# untitled.net
KiCad netlist of a schematic drawn in EAGLE
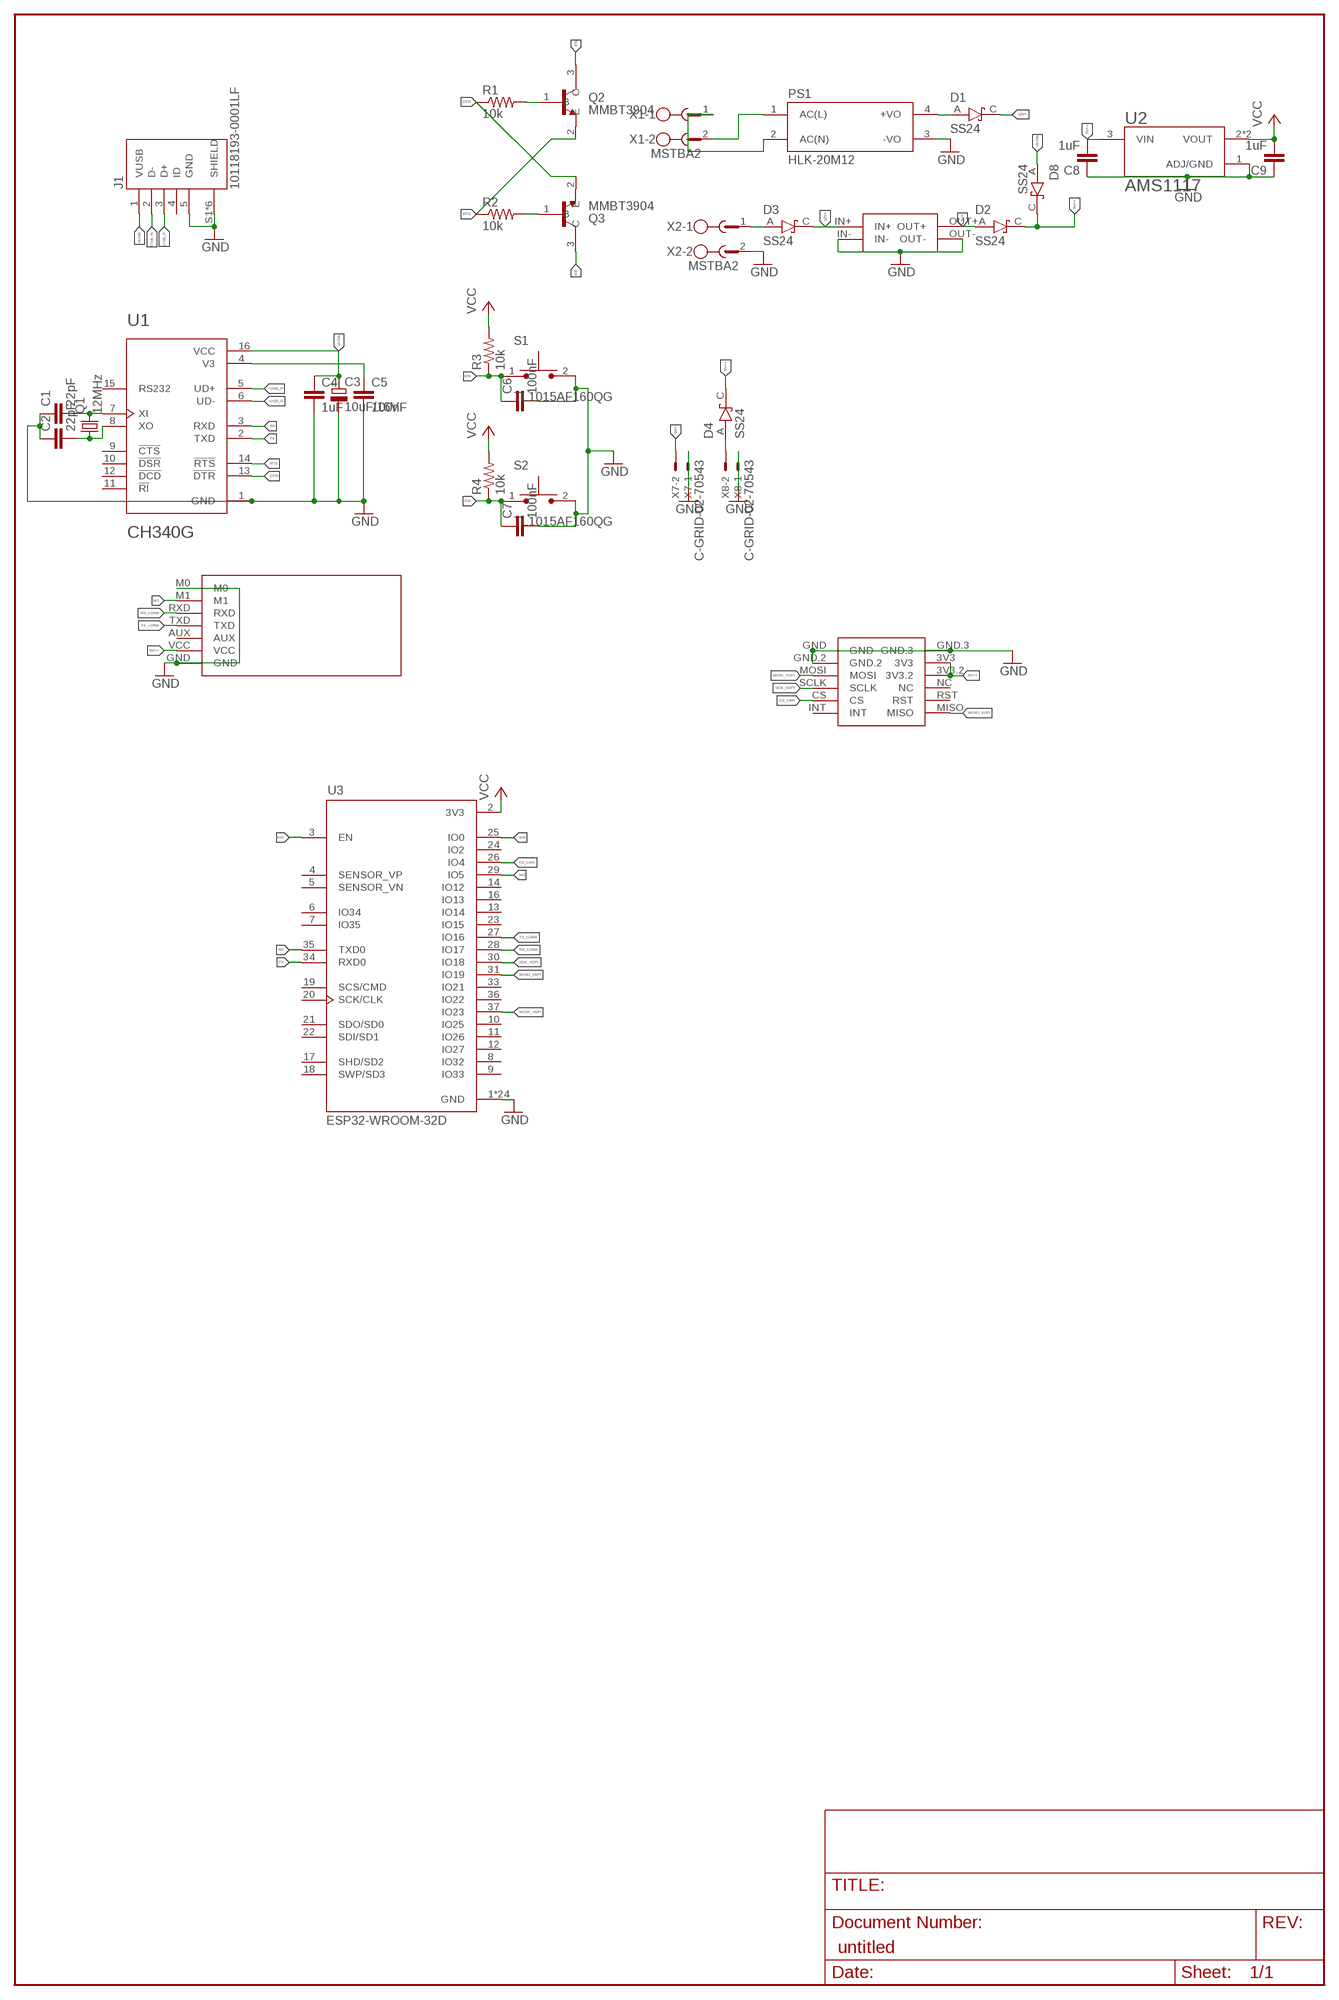
[diagram p0: schematic, sheet 1]

(export (version "E")
  (design (tool "Eeschema 10.0.6"))
  (components
    (comp (ref "C1")
      (value "22pF")
      (footprint "eagle-import:C0805K")
      (libsource (lib "eagle-import") (part "C-EUC0805K"))
    )
    (comp (ref "C2")
      (value "22pF")
      (footprint "eagle-import:C0805K")
      (libsource (lib "eagle-import") (part "C-EUC0805K"))
    )
    (comp (ref "C3")
      (value "10uF/16V")
      (footprint "eagle-import:153CLV-0505")
      (libsource (lib "eagle-import") (part "CPOL-EU153CLV-0505"))
    )
    (comp (ref "C4")
      (value "1uF")
      (footprint "eagle-import:C0805K")
      (libsource (lib "eagle-import") (part "C-EUC0805K"))
    )
    (comp (ref "C5")
      (value "100nF")
      (footprint "eagle-import:C0805K")
      (libsource (lib "eagle-import") (part "C-EUC0805K"))
    )
    (comp (ref "C6")
      (value "100nF")
      (footprint "eagle-import:C0805K")
      (libsource (lib "eagle-import") (part "C-EUC0805K"))
    )
    (comp (ref "C7")
      (value "100nF")
      (footprint "eagle-import:C0805K")
      (libsource (lib "eagle-import") (part "C-EUC0805K"))
    )
    (comp (ref "C8")
      (value "1uF")
      (footprint "eagle-import:C0805K")
      (libsource (lib "eagle-import") (part "C-EUC0805K"))
    )
    (comp (ref "C9")
      (value "1uF")
      (footprint "eagle-import:C0805K")
      (libsource (lib "eagle-import") (part "C-EUC0805K"))
    )
    (comp (ref "D1")
      (value "SS24")
      (footprint "eagle-import:DIOM5336X265N")
      (fields (field (name "MF") "ON Semiconductor"))
      (libsource (lib "eagle-import") (part "SS24"))
    )
    (comp (ref "D2")
      (value "SS24")
      (footprint "eagle-import:DIOM5336X265N")
      (fields (field (name "MF") "ON Semiconductor"))
      (libsource (lib "eagle-import") (part "SS24"))
    )
    (comp (ref "D3")
      (value "SS24")
      (footprint "eagle-import:DIOM5336X265N")
      (fields (field (name "MF") "ON Semiconductor"))
      (libsource (lib "eagle-import") (part "SS24"))
    )
    (comp (ref "D4")
      (value "SS24")
      (footprint "eagle-import:DIOM5336X265N")
      (fields (field (name "MF") "ON Semiconductor"))
      (libsource (lib "eagle-import") (part "SS24"))
    )
    (comp (ref "D8")
      (value "SS24")
      (footprint "eagle-import:DIOM5336X265N")
      (fields (field (name "MF") "ON Semiconductor"))
      (libsource (lib "eagle-import") (part "SS24"))
    )
    (comp (ref "EBYTEE220-900T22D1")
      (value "EBYTEE220-900T22D")
      (footprint "eagle-import:EBYTEE220-900T22D")
      (libsource (lib "eagle-import") (part "EBYTEE220-900T22D"))
    )
    (comp (ref "J1")
      (value "10118193-0001LF")
      (footprint "eagle-import:FCI_10118193-0001LF")
      (fields (field (name "MF") "FCI"))
      (libsource (lib "eagle-import") (part "10118193-0001LF"))
    )
    (comp (ref "MINI1")
      (value "MINI560")
      (footprint "eagle-import:MINI560")
      (libsource (lib "eagle-import") (part "MINI560"))
    )
    (comp (ref "PS1")
      (value "HLK-20M12")
      (footprint "eagle-import:CONV_HLK-20M12")
      (fields (field (name "MF") "Hi-link"))
      (libsource (lib "eagle-import") (part "HLK-20M12"))
    )
    (comp (ref "Q1")
      (value "12MHz")
      (footprint "eagle-import:SM49")
      (libsource (lib "eagle-import") (part "CRYSTALSM49"))
    )
    (comp (ref "Q2")
      (value "MMBT3904")
      (footprint "eagle-import:SOT95P240X120-3N")
      (fields (field (name "MF") "ON Semiconductor"))
      (libsource (lib "eagle-import") (part "MMBT3904"))
    )
    (comp (ref "Q3")
      (value "MMBT3904")
      (footprint "eagle-import:SOT95P240X120-3N")
      (fields (field (name "MF") "ON Semiconductor"))
      (libsource (lib "eagle-import") (part "MMBT3904"))
    )
    (comp (ref "R1")
      (value "10k")
      (footprint "eagle-import:M0805")
      (libsource (lib "eagle-import") (part "R-US_M0805"))
    )
    (comp (ref "R2")
      (value "10k")
      (footprint "eagle-import:M0805")
      (libsource (lib "eagle-import") (part "R-US_M0805"))
    )
    (comp (ref "R3")
      (value "10k")
      (footprint "eagle-import:M0805")
      (libsource (lib "eagle-import") (part "R-US_M0805"))
    )
    (comp (ref "R4")
      (value "10k")
      (footprint "eagle-import:M0805")
      (libsource (lib "eagle-import") (part "R-US_M0805"))
    )
    (comp (ref "S1")
      (value "TL1015AF160QG")
      (footprint "eagle-import:SW_TL1015AF160QG")
      (fields (field (name "MF") "E-Switch"))
      (libsource (lib "eagle-import") (part "TL1015AF160QG"))
    )
    (comp (ref "S2")
      (value "TL1015AF160QG")
      (footprint "eagle-import:SW_TL1015AF160QG")
      (fields (field (name "MF") "E-Switch"))
      (libsource (lib "eagle-import") (part "TL1015AF160QG"))
    )
    (comp (ref "U$1")
      (value "MINI_W5500")
      (footprint "eagle-import:MINI_W5500")
      (libsource (lib "eagle-import") (part "MINI_W5500"))
    )
    (comp (ref "U1")
      (value "CH340G")
      (footprint "eagle-import:SOIC127P600X180-16N")
      (fields (field (name "MF") "WCH") (field (name "MP") "Ch340G"))
      (libsource (lib "eagle-import") (part "CH340G"))
    )
    (comp (ref "U2")
      (value "AMS1117")
      (footprint "eagle-import:SOT229P700X180-4N")
      (fields (field (name "MF") "Advanced Monolithic Systems"))
      (libsource (lib "eagle-import") (part "AMS1117"))
    )
    (comp (ref "U3")
      (value "ESP32-WROOM-32D")
      (footprint "eagle-import:MODULE_ESP32-WROOM-32D")
      (fields (field (name "MF") "Espressif Systems"))
      (libsource (lib "eagle-import") (part "ESP32-WROOM-32D"))
    )
    (comp (ref "X1")
      (value "MSTBA2")
      (footprint "eagle-import:MSTBA2")
      (fields (field (name "MF") "FARNELL") (field (name "MPN") "1757242"))
      (libsource (lib "eagle-import") (part "MSTBA2"))
    )
    (comp (ref "X2")
      (value "MSTBA2")
      (footprint "eagle-import:MSTBA2")
      (fields (field (name "MF") "FARNELL") (field (name "MPN") "1757242"))
      (libsource (lib "eagle-import") (part "MSTBA2"))
    )
    (comp (ref "X7")
      (value "C-GRID-02-70543")
      (footprint "eagle-import:70543-02")
      (fields (field (name "MF") "MOLEX"))
      (libsource (lib "eagle-import") (part "C-GRID-02-70543"))
    )
    (comp (ref "X8")
      (value "C-GRID-02-70543")
      (footprint "eagle-import:70543-02")
      (fields (field (name "MF") "MOLEX"))
      (libsource (lib "eagle-import") (part "C-GRID-02-70543"))
    )
  )
  (nets
    (net (code "1") (name "5V+") (class "Default")
      (node (ref "D2") (pin "A") (pinfunction "A_A") (pintype "passive"))
      (node (ref "MINI1") (pin "OUT+") (pinfunction "OUT+_OUT+") (pintype "bidirectional"))
      (node (ref "X7") (pin "2") (pinfunction "S_2") (pintype "passive"))
    )
    (net (code "2") (name "5V++") (class "Default")
      (node (ref "C8") (pin "2") (pinfunction "2_2") (pintype "passive"))
      (node (ref "D2") (pin "C") (pinfunction "K_C") (pintype "passive"))
      (node (ref "D4") (pin "C") (pinfunction "K_C") (pintype "passive"))
      (node (ref "D8") (pin "C") (pinfunction "K_C") (pintype "passive"))
      (node (ref "EBYTEE220-900T22D1") (pin "VCC") (pinfunction "VCC_VCC") (pintype "bidirectional"))
      (node (ref "U$1") (pin "3V3") (pinfunction "3V3_3V3") (pintype "bidirectional"))
      (node (ref "U$1") (pin "3V3.2") (pinfunction "3V3.2_3V3.2") (pintype "bidirectional"))
      (node (ref "U2") (pin "3") (pinfunction "VIN_3") (pintype "input"))
    )
    (net (code "3") (name "12V+") (class "Default")
      (node (ref "D1") (pin "C") (pinfunction "K_C") (pintype "passive"))
      (node (ref "D3") (pin "C") (pinfunction "K_C") (pintype "passive"))
      (node (ref "MINI1") (pin "IN+") (pinfunction "IN+_IN+") (pintype "bidirectional"))
    )
    (net (code "4") (name "CS_LAN") (class "Default")
      (node (ref "U$1") (pin "CS") (pinfunction "CS_CS") (pintype "bidirectional"))
      (node (ref "U3") (pin "26") (pinfunction "IO4_26") (pintype "bidirectional"))
    )
    (net (code "5") (name "DTR") (class "Default")
      (node (ref "Q3") (pin "2") (pinfunction "E_2") (pintype "passive"))
      (node (ref "R1") (pin "1") (pinfunction "1_1") (pintype "passive"))
      (node (ref "U1") (pin "13") (pinfunction "~{DTR}_13") (pintype "output"))
    )
    (net (code "6") (name "EN") (class "Default")
      (node (ref "C6") (pin "1") (pinfunction "1_1") (pintype "passive"))
      (node (ref "Q2") (pin "3") (pinfunction "C_3") (pintype "passive"))
      (node (ref "R3") (pin "1") (pinfunction "1_1") (pintype "passive"))
      (node (ref "S1") (pin "1") (pinfunction "1_1") (pintype "passive"))
      (node (ref "U3") (pin "3") (pinfunction "EN_3") (pintype "input"))
    )
    (net (code "7") (name "GND") (class "Default")
      (node (ref "C1") (pin "1") (pinfunction "1_1") (pintype "passive"))
      (node (ref "C2") (pin "1") (pinfunction "1_1") (pintype "passive"))
      (node (ref "C3") (pin "-") (pinfunction "-_-") (pintype "passive"))
      (node (ref "C4") (pin "2") (pinfunction "2_2") (pintype "passive"))
      (node (ref "C5") (pin "2") (pinfunction "2_2") (pintype "passive"))
      (node (ref "C6") (pin "2") (pinfunction "2_2") (pintype "passive"))
      (node (ref "C7") (pin "2") (pinfunction "2_2") (pintype "passive"))
      (node (ref "C8") (pin "1") (pinfunction "1_1") (pintype "passive"))
      (node (ref "C9") (pin "1") (pinfunction "1_1") (pintype "passive"))
      (node (ref "EBYTEE220-900T22D1") (pin "GND") (pinfunction "GND_GND") (pintype "bidirectional"))
      (node (ref "EBYTEE220-900T22D1") (pin "M0") (pinfunction "M0_M0") (pintype "bidirectional"))
      (node (ref "J1") (pin "5") (pinfunction "GND_5") (pintype "passive"))
      (node (ref "J1") (pin "S1") (pinfunction "SHIELD_S1") (pintype "passive"))
      (node (ref "J1") (pin "S2") (pinfunction "SHIELD_S2") (pintype "passive"))
      (node (ref "J1") (pin "S3") (pinfunction "SHIELD_S3") (pintype "passive"))
      (node (ref "J1") (pin "S4") (pinfunction "SHIELD_S4") (pintype "passive"))
      (node (ref "J1") (pin "S5") (pinfunction "SHIELD_S5") (pintype "passive"))
      (node (ref "J1") (pin "S6") (pinfunction "SHIELD_S6") (pintype "passive"))
      (node (ref "MINI1") (pin "IN-") (pinfunction "IN-_IN-") (pintype "bidirectional"))
      (node (ref "MINI1") (pin "OUT-") (pinfunction "OUT-_OUT-") (pintype "bidirectional"))
      (node (ref "PS1") (pin "3") (pinfunction "-VO_3") (pintype "output"))
      (node (ref "S1") (pin "2") (pinfunction "2_2") (pintype "passive"))
      (node (ref "S2") (pin "2") (pinfunction "2_2") (pintype "passive"))
      (node (ref "U$1") (pin "GND") (pinfunction "GND_GND") (pintype "bidirectional"))
      (node (ref "U$1") (pin "GND.2") (pinfunction "GND.2_GND.2") (pintype "bidirectional"))
      (node (ref "U$1") (pin "GND.3") (pinfunction "GND.3_GND.3") (pintype "bidirectional"))
      (node (ref "U1") (pin "1") (pinfunction "GND_1") (pintype "power_in"))
      (node (ref "U2") (pin "1") (pinfunction "ADJ/GND_1") (pintype "power_in"))
      (node (ref "U3") (pin "1") (pinfunction "GND_1") (pintype "power_in"))
      (node (ref "U3") (pin "15") (pinfunction "GND_15") (pintype "power_in"))
      (node (ref "U3") (pin "38") (pinfunction "GND_38") (pintype "power_in"))
      (node (ref "U3") (pin "39_1") (pinfunction "GND_39_1") (pintype "power_in"))
      (node (ref "U3") (pin "39_10") (pinfunction "GND_39_10") (pintype "power_in"))
      (node (ref "U3") (pin "39_11") (pinfunction "GND_39_11") (pintype "power_in"))
      (node (ref "U3") (pin "39_12") (pinfunction "GND_39_12") (pintype "power_in"))
      (node (ref "U3") (pin "39_13") (pinfunction "GND_39_13") (pintype "power_in"))
      (node (ref "U3") (pin "39_14") (pinfunction "GND_39_14") (pintype "power_in"))
      (node (ref "U3") (pin "39_15") (pinfunction "GND_39_15") (pintype "power_in"))
      (node (ref "U3") (pin "39_16") (pinfunction "GND_39_16") (pintype "power_in"))
      (node (ref "U3") (pin "39_17") (pinfunction "GND_39_17") (pintype "power_in"))
      (node (ref "U3") (pin "39_18") (pinfunction "GND_39_18") (pintype "power_in"))
      (node (ref "U3") (pin "39_19") (pinfunction "GND_39_19") (pintype "power_in"))
      (node (ref "U3") (pin "39_2") (pinfunction "GND_39_2") (pintype "power_in"))
      (node (ref "U3") (pin "39_20") (pinfunction "GND_39_20") (pintype "power_in"))
      (node (ref "U3") (pin "39_21") (pinfunction "GND_39_21") (pintype "power_in"))
      (node (ref "U3") (pin "39_3") (pinfunction "GND_39_3") (pintype "power_in"))
      (node (ref "U3") (pin "39_4") (pinfunction "GND_39_4") (pintype "power_in"))
      (node (ref "U3") (pin "39_5") (pinfunction "GND_39_5") (pintype "power_in"))
      (node (ref "U3") (pin "39_6") (pinfunction "GND_39_6") (pintype "power_in"))
      (node (ref "U3") (pin "39_7") (pinfunction "GND_39_7") (pintype "power_in"))
      (node (ref "U3") (pin "39_8") (pinfunction "GND_39_8") (pintype "power_in"))
      (node (ref "U3") (pin "39_9") (pinfunction "GND_39_9") (pintype "power_in"))
      (node (ref "X2") (pin "2") (pinfunction "1_2") (pintype "passive"))
      (node (ref "X7") (pin "1") (pinfunction "S_1") (pintype "passive"))
      (node (ref "X8") (pin "1") (pinfunction "S_1") (pintype "passive"))
    )
    (net (code "8") (name "IO0") (class "Default")
      (node (ref "C7") (pin "1") (pinfunction "1_1") (pintype "passive"))
      (node (ref "Q3") (pin "3") (pinfunction "C_3") (pintype "passive"))
      (node (ref "R4") (pin "1") (pinfunction "1_1") (pintype "passive"))
      (node (ref "S2") (pin "1") (pinfunction "1_1") (pintype "passive"))
      (node (ref "U3") (pin "25") (pinfunction "IO0_25") (pintype "bidirectional"))
    )
    (net (code "9") (name "M1") (class "Default")
      (node (ref "EBYTEE220-900T22D1") (pin "M1") (pinfunction "M1_M1") (pintype "bidirectional"))
      (node (ref "U3") (pin "29") (pinfunction "IO5_29") (pintype "bidirectional"))
    )
    (net (code "10") (name "MISO_VSPI") (class "Default")
      (node (ref "U$1") (pin "MISO") (pinfunction "MISO_MISO") (pintype "bidirectional"))
      (node (ref "U3") (pin "31") (pinfunction "IO19_31") (pintype "bidirectional"))
    )
    (net (code "11") (name "MOSI_VSPI") (class "Default")
      (node (ref "U$1") (pin "MOSI") (pinfunction "MOSI_MOSI") (pintype "bidirectional"))
      (node (ref "U3") (pin "37") (pinfunction "IO23_37") (pintype "bidirectional"))
    )
    (net (code "12") (name "Net-(D3-PadA)") (class "Default")
      (node (ref "D3") (pin "A") (pinfunction "A_A") (pintype "passive"))
      (node (ref "X2") (pin "1") (pinfunction "1_1") (pintype "passive"))
    )
    (net (code "13") (name "Net-(PS1-+VO)") (class "Default")
      (node (ref "D1") (pin "A") (pinfunction "A_A") (pintype "passive"))
      (node (ref "PS1") (pin "4") (pinfunction "+VO_4") (pintype "output"))
    )
    (net (code "14") (name "Net-(PS1-AC(L))") (class "Default")
      (node (ref "PS1") (pin "1") (pinfunction "AC(L)_1") (pintype "input"))
      (node (ref "X1") (pin "2") (pinfunction "1_2") (pintype "passive"))
    )
    (net (code "15") (name "Net-(PS1-AC(N))") (class "Default")
      (node (ref "PS1") (pin "2") (pinfunction "AC(N)_2") (pintype "input"))
      (node (ref "X1") (pin "1") (pinfunction "1_1") (pintype "passive"))
    )
    (net (code "16") (name "Net-(Q2-B)") (class "Default")
      (node (ref "Q2") (pin "1") (pinfunction "B_1") (pintype "passive"))
      (node (ref "R1") (pin "2") (pinfunction "2_2") (pintype "passive"))
    )
    (net (code "17") (name "Net-(Q3-B)") (class "Default")
      (node (ref "Q3") (pin "1") (pinfunction "B_1") (pintype "passive"))
      (node (ref "R2") (pin "2") (pinfunction "2_2") (pintype "passive"))
    )
    (net (code "18") (name "Net-(U1-V3)") (class "Default")
      (node (ref "C5") (pin "1") (pinfunction "1_1") (pintype "passive"))
      (node (ref "U1") (pin "4") (pinfunction "V3_4") (pintype "power_in"))
    )
    (net (code "19") (name "Net-(U1-XI)") (class "Default")
      (node (ref "C1") (pin "2") (pinfunction "2_2") (pintype "passive"))
      (node (ref "Q1") (pin "2") (pinfunction "2_2") (pintype "passive"))
      (node (ref "U1") (pin "7") (pinfunction "XI_7") (pintype "input"))
    )
    (net (code "20") (name "Net-(U1-XO)") (class "Default")
      (node (ref "C2") (pin "2") (pinfunction "2_2") (pintype "passive"))
      (node (ref "Q1") (pin "1") (pinfunction "1_1") (pintype "passive"))
      (node (ref "U1") (pin "8") (pinfunction "XO_8") (pintype "output"))
    )
    (net (code "21") (name "Net-(X8B-S)") (class "Default")
      (node (ref "D4") (pin "A") (pinfunction "A_A") (pintype "passive"))
      (node (ref "X8") (pin "2") (pinfunction "S_2") (pintype "passive"))
    )
    (net (code "22") (name "RTS") (class "Default")
      (node (ref "Q2") (pin "2") (pinfunction "E_2") (pintype "passive"))
      (node (ref "R2") (pin "1") (pinfunction "1_1") (pintype "passive"))
      (node (ref "U1") (pin "14") (pinfunction "~{RTS}_14") (pintype "output"))
    )
    (net (code "23") (name "RX") (class "Default")
      (node (ref "U1") (pin "3") (pinfunction "RXD_3") (pintype "input"))
      (node (ref "U3") (pin "35") (pinfunction "TXD0_35") (pintype "bidirectional"))
    )
    (net (code "24") (name "RX_LORA") (class "Default")
      (node (ref "EBYTEE220-900T22D1") (pin "RXD") (pinfunction "RXD_RXD") (pintype "bidirectional"))
      (node (ref "U3") (pin "28") (pinfunction "IO17_28") (pintype "bidirectional"))
    )
    (net (code "25") (name "SCK_VSPI") (class "Default")
      (node (ref "U$1") (pin "SCLK") (pinfunction "SCLK_SCLK") (pintype "bidirectional"))
      (node (ref "U3") (pin "30") (pinfunction "IO18_30") (pintype "bidirectional"))
    )
    (net (code "26") (name "TX") (class "Default")
      (node (ref "U1") (pin "2") (pinfunction "TXD_2") (pintype "output"))
      (node (ref "U3") (pin "34") (pinfunction "RXD0_34") (pintype "bidirectional"))
    )
    (net (code "27") (name "TX_LORA") (class "Default")
      (node (ref "EBYTEE220-900T22D1") (pin "TXD") (pinfunction "TXD_TXD") (pintype "bidirectional"))
      (node (ref "U3") (pin "27") (pinfunction "IO16_27") (pintype "bidirectional"))
    )
    (net (code "28") (name "USB_N") (class "Default")
      (node (ref "J1") (pin "2") (pinfunction "D-_2") (pintype "passive"))
      (node (ref "U1") (pin "6") (pinfunction "UD-_6") (pintype "bidirectional"))
    )
    (net (code "29") (name "USB_P") (class "Default")
      (node (ref "J1") (pin "3") (pinfunction "D+_3") (pintype "passive"))
      (node (ref "U1") (pin "5") (pinfunction "UD+_5") (pintype "bidirectional"))
    )
    (net (code "30") (name "VCC") (class "Default")
      (node (ref "C9") (pin "2") (pinfunction "2_2") (pintype "passive"))
      (node (ref "R3") (pin "2") (pinfunction "2_2") (pintype "passive"))
      (node (ref "R4") (pin "2") (pinfunction "2_2") (pintype "passive"))
      (node (ref "U2") (pin "2") (pinfunction "VOUT_2") (pintype "output"))
      (node (ref "U2") (pin "4") (pinfunction "VOUT_4") (pintype "output"))
      (node (ref "U3") (pin "2") (pinfunction "3V3_2") (pintype "power_in"))
    )
    (net (code "31") (name "VUSB") (class "Default")
      (node (ref "C3") (pin "+") (pinfunction "+_+") (pintype "passive"))
      (node (ref "C4") (pin "1") (pinfunction "1_1") (pintype "passive"))
      (node (ref "D8") (pin "A") (pinfunction "A_A") (pintype "passive"))
      (node (ref "J1") (pin "1") (pinfunction "VUSB_1") (pintype "passive"))
      (node (ref "U1") (pin "16") (pinfunction "VCC_16") (pintype "power_in"))
    )
    (net (code "32") (name "unconnected-(EBYTEE220-900T22D1-PadAUX)") (class "Default")
      (node (ref "EBYTEE220-900T22D1") (pin "AUX") (pinfunction "AUX_AUX") (pintype "bidirectional"))
    )
    (net (code "33") (name "unconnected-(J1-ID-Pad4)") (class "Default")
      (node (ref "J1") (pin "4") (pinfunction "ID_4") (pintype "passive"))
    )
    (net (code "34") (name "unconnected-(U$1-PadINT)") (class "Default")
      (node (ref "U$1") (pin "INT") (pinfunction "INT_INT") (pintype "bidirectional"))
    )
    (net (code "35") (name "unconnected-(U$1-PadNC)") (class "Default")
      (node (ref "U$1") (pin "NC") (pinfunction "NC_NC") (pintype "bidirectional"))
    )
    (net (code "36") (name "unconnected-(U$1-PadRST)") (class "Default")
      (node (ref "U$1") (pin "RST") (pinfunction "RST_RST") (pintype "bidirectional"))
    )
    (net (code "37") (name "unconnected-(U1-RS232-Pad15)") (class "Default")
      (node (ref "U1") (pin "15") (pinfunction "RS232_15") (pintype "input"))
    )
    (net (code "38") (name "unconnected-(U1-~{CTS}-Pad9)") (class "Default")
      (node (ref "U1") (pin "9") (pinfunction "~{CTS}_9") (pintype "input"))
    )
    (net (code "39") (name "unconnected-(U1-~{DCD}-Pad12)") (class "Default")
      (node (ref "U1") (pin "12") (pinfunction "~{DCD}_12") (pintype "input"))
    )
    (net (code "40") (name "unconnected-(U1-~{DSR}-Pad10)") (class "Default")
      (node (ref "U1") (pin "10") (pinfunction "~{DSR}_10") (pintype "input"))
    )
    (net (code "41") (name "unconnected-(U1-~{RI}-Pad11)") (class "Default")
      (node (ref "U1") (pin "11") (pinfunction "~{RI}_11") (pintype "input"))
    )
    (net (code "42") (name "unconnected-(U3-IO2-Pad24)") (class "Default")
      (node (ref "U3") (pin "24") (pinfunction "IO2_24") (pintype "bidirectional"))
    )
    (net (code "43") (name "unconnected-(U3-IO12-Pad14)") (class "Default")
      (node (ref "U3") (pin "14") (pinfunction "IO12_14") (pintype "bidirectional"))
    )
    (net (code "44") (name "unconnected-(U3-IO13-Pad16)") (class "Default")
      (node (ref "U3") (pin "16") (pinfunction "IO13_16") (pintype "bidirectional"))
    )
    (net (code "45") (name "unconnected-(U3-IO14-Pad13)") (class "Default")
      (node (ref "U3") (pin "13") (pinfunction "IO14_13") (pintype "bidirectional"))
    )
    (net (code "46") (name "unconnected-(U3-IO15-Pad23)") (class "Default")
      (node (ref "U3") (pin "23") (pinfunction "IO15_23") (pintype "bidirectional"))
    )
    (net (code "47") (name "unconnected-(U3-IO21-Pad33)") (class "Default")
      (node (ref "U3") (pin "33") (pinfunction "IO21_33") (pintype "bidirectional"))
    )
    (net (code "48") (name "unconnected-(U3-IO22-Pad36)") (class "Default")
      (node (ref "U3") (pin "36") (pinfunction "IO22_36") (pintype "bidirectional"))
    )
    (net (code "49") (name "unconnected-(U3-IO25-Pad10)") (class "Default")
      (node (ref "U3") (pin "10") (pinfunction "IO25_10") (pintype "bidirectional"))
    )
    (net (code "50") (name "unconnected-(U3-IO26-Pad11)") (class "Default")
      (node (ref "U3") (pin "11") (pinfunction "IO26_11") (pintype "bidirectional"))
    )
    (net (code "51") (name "unconnected-(U3-IO27-Pad12)") (class "Default")
      (node (ref "U3") (pin "12") (pinfunction "IO27_12") (pintype "bidirectional"))
    )
    (net (code "52") (name "unconnected-(U3-IO32-Pad8)") (class "Default")
      (node (ref "U3") (pin "8") (pinfunction "IO32_8") (pintype "bidirectional"))
    )
    (net (code "53") (name "unconnected-(U3-IO33-Pad9)") (class "Default")
      (node (ref "U3") (pin "9") (pinfunction "IO33_9") (pintype "bidirectional"))
    )
    (net (code "54") (name "unconnected-(U3-IO34-Pad6)") (class "Default")
      (node (ref "U3") (pin "6") (pinfunction "IO34_6") (pintype "input"))
    )
    (net (code "55") (name "unconnected-(U3-IO35-Pad7)") (class "Default")
      (node (ref "U3") (pin "7") (pinfunction "IO35_7") (pintype "input"))
    )
    (net (code "56") (name "unconnected-(U3-SCK{slash}CLK-Pad20)") (class "Default")
      (node (ref "U3") (pin "20") (pinfunction "SCK/CLK_20") (pintype "bidirectional"))
    )
    (net (code "57") (name "unconnected-(U3-SCS{slash}CMD-Pad19)") (class "Default")
      (node (ref "U3") (pin "19") (pinfunction "SCS/CMD_19") (pintype "bidirectional"))
    )
    (net (code "58") (name "unconnected-(U3-SDI{slash}SD1-Pad22)") (class "Default")
      (node (ref "U3") (pin "22") (pinfunction "SDI/SD1_22") (pintype "bidirectional"))
    )
    (net (code "59") (name "unconnected-(U3-SDO{slash}SD0-Pad21)") (class "Default")
      (node (ref "U3") (pin "21") (pinfunction "SDO/SD0_21") (pintype "bidirectional"))
    )
    (net (code "60") (name "unconnected-(U3-SENSOR_VN-Pad5)") (class "Default")
      (node (ref "U3") (pin "5") (pinfunction "SENSOR_VN_5") (pintype "input"))
    )
    (net (code "61") (name "unconnected-(U3-SENSOR_VP-Pad4)") (class "Default")
      (node (ref "U3") (pin "4") (pinfunction "SENSOR_VP_4") (pintype "input"))
    )
    (net (code "62") (name "unconnected-(U3-SHD{slash}SD2-Pad17)") (class "Default")
      (node (ref "U3") (pin "17") (pinfunction "SHD/SD2_17") (pintype "bidirectional"))
    )
    (net (code "63") (name "unconnected-(U3-SWP{slash}SD3-Pad18)") (class "Default")
      (node (ref "U3") (pin "18") (pinfunction "SWP/SD3_18") (pintype "bidirectional"))
    )
  )
)
